# PL_Ethernet.net
KiCad netlist of a schematic drawn in Altium Designer
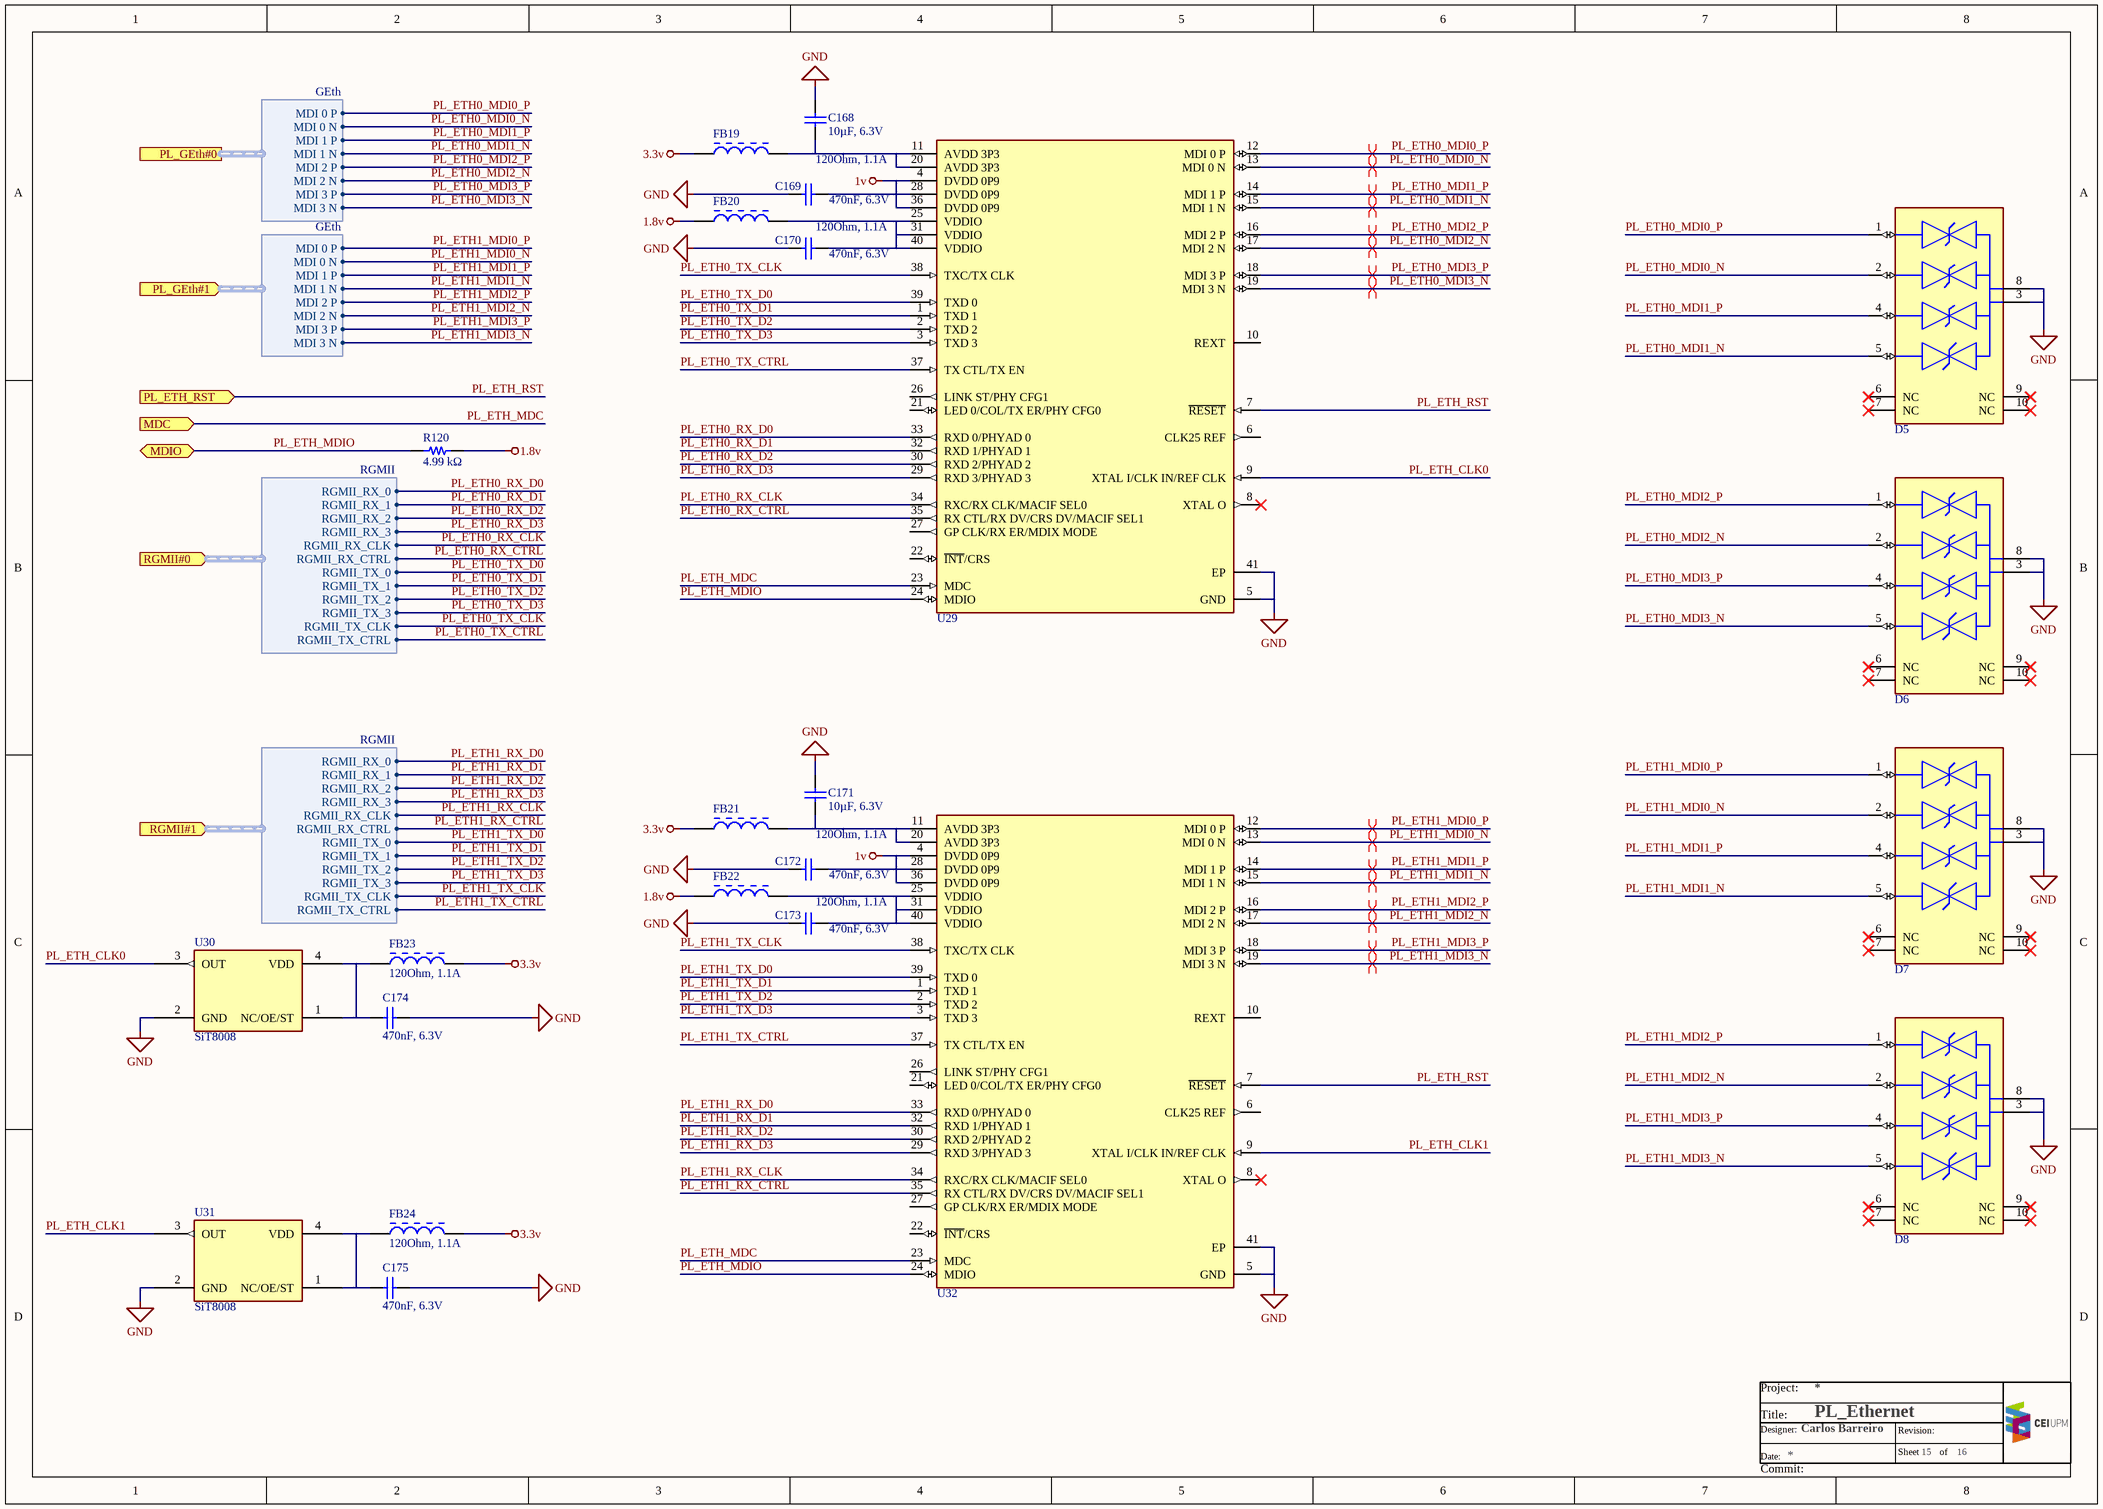
[diagram p0: PL_Ethernet.SchDoc]

(export (version "E")
  (design (tool "Eeschema 10.0.6"))
  (components
    (comp (ref "C168")
      (value "10µF, 6.3V")
      (footprint "WURTH_WCAP-CSGP_0402")
      (description "WCAP-CSGP Multilayer Ceramic Chip Capacitor, General Purpose, size 0402, X5R, 10uF, 6.3V")
      (fields
        (field (name "MANUFACTURER PART NUMBER") "885012105020")
        (field (name "MANUFACTURER") "Wurth Elektronik")
      )
      (libsource (lib "SpaceVNXBaseBoard") (part "885012105020"))
    )
    (comp (ref "C169")
      (value "470nF, 6.3V")
      (footprint "WURTH_WCAP-CSGP_0402")
      (description "WCAP-CSGP Multilayer Ceramic Chip Capacitor, General Purpose, size 0402, X5R, 470nF, 6.3V")
      (fields
        (field (name "MANUFACTURER PART NUMBER") "885012105004")
        (field (name "MANUFACTURER") "Wurth Elektronik")
      )
      (libsource (lib "SpaceVNXBaseBoard") (part "885012105004"))
    )
    (comp (ref "C170")
      (value "470nF, 6.3V")
      (footprint "WURTH_WCAP-CSGP_0402")
      (description "WCAP-CSGP Multilayer Ceramic Chip Capacitor, General Purpose, size 0402, X5R, 470nF, 6.3V")
      (fields
        (field (name "MANUFACTURER PART NUMBER") "885012105004")
        (field (name "MANUFACTURER") "Wurth Elektronik")
      )
      (libsource (lib "SpaceVNXBaseBoard") (part "885012105004"))
    )
    (comp (ref "C171")
      (value "10µF, 6.3V")
      (footprint "WURTH_WCAP-CSGP_0402")
      (description "WCAP-CSGP Multilayer Ceramic Chip Capacitor, General Purpose, size 0402, X5R, 10uF, 6.3V")
      (fields
        (field (name "MANUFACTURER PART NUMBER") "885012105020")
        (field (name "MANUFACTURER") "Wurth Elektronik")
      )
      (libsource (lib "SpaceVNXBaseBoard") (part "885012105020"))
    )
    (comp (ref "C172")
      (value "470nF, 6.3V")
      (footprint "WURTH_WCAP-CSGP_0402")
      (description "WCAP-CSGP Multilayer Ceramic Chip Capacitor, General Purpose, size 0402, X5R, 470nF, 6.3V")
      (fields
        (field (name "MANUFACTURER PART NUMBER") "885012105004")
        (field (name "MANUFACTURER") "Wurth Elektronik")
      )
      (libsource (lib "SpaceVNXBaseBoard") (part "885012105004"))
    )
    (comp (ref "C173")
      (value "470nF, 6.3V")
      (footprint "WURTH_WCAP-CSGP_0402")
      (description "WCAP-CSGP Multilayer Ceramic Chip Capacitor, General Purpose, size 0402, X5R, 470nF, 6.3V")
      (fields
        (field (name "MANUFACTURER PART NUMBER") "885012105004")
        (field (name "MANUFACTURER") "Wurth Elektronik")
      )
      (libsource (lib "SpaceVNXBaseBoard") (part "885012105004"))
    )
    (comp (ref "C174")
      (value "470nF, 6.3V")
      (footprint "WURTH_WCAP-CSGP_0402")
      (description "WCAP-CSGP Multilayer Ceramic Chip Capacitor, General Purpose, size 0402, X5R, 470nF, 6.3V")
      (fields
        (field (name "MANUFACTURER PART NUMBER") "885012105004")
        (field (name "MANUFACTURER") "Wurth Elektronik")
      )
      (libsource (lib "SpaceVNXBaseBoard") (part "885012105004"))
    )
    (comp (ref "C175")
      (value "470nF, 6.3V")
      (footprint "WURTH_WCAP-CSGP_0402")
      (description "WCAP-CSGP Multilayer Ceramic Chip Capacitor, General Purpose, size 0402, X5R, 470nF, 6.3V")
      (fields
        (field (name "MANUFACTURER PART NUMBER") "885012105004")
        (field (name "MANUFACTURER") "Wurth Elektronik")
      )
      (libsource (lib "SpaceVNXBaseBoard") (part "885012105004"))
    )
    (comp (ref "D5")
      (value "ESD204DQAR")
      (footprint "TEXAS_USON10")
      (description "ESD204 4-Channel Low-Capacitance Surge and ESD Protection Diode")
      (libsource (lib "SpaceVNXBaseBoard") (part "ESD204DQAR"))
    )
    (comp (ref "D6")
      (value "ESD204DQAR")
      (footprint "TEXAS_USON10")
      (description "ESD204 4-Channel Low-Capacitance Surge and ESD Protection Diode")
      (libsource (lib "SpaceVNXBaseBoard") (part "ESD204DQAR"))
    )
    (comp (ref "D7")
      (value "ESD204DQAR")
      (footprint "TEXAS_USON10")
      (description "ESD204 4-Channel Low-Capacitance Surge and ESD Protection Diode")
      (libsource (lib "SpaceVNXBaseBoard") (part "ESD204DQAR"))
    )
    (comp (ref "D8")
      (value "ESD204DQAR")
      (footprint "TEXAS_USON10")
      (description "ESD204 4-Channel Low-Capacitance Surge and ESD Protection Diode")
      (libsource (lib "SpaceVNXBaseBoard") (part "ESD204DQAR"))
    )
    (comp (ref "FB19")
      (value "120Ohm, 1.1A")
      (footprint "WURTH-CBF_0402")
      (description "WE-CBF SMT EMI Suppression Ferrite Bead, size 0402, 120Ohm, 1.1A")
      (fields
        (field (name "MANUFACTURER PART NUMBER") "74279271")
        (field (name "MANUFACTURER") "Wurth Elektronik")
      )
      (libsource (lib "SpaceVNXBaseBoard") (part "74279271"))
    )
    (comp (ref "FB20")
      (value "120Ohm, 1.1A")
      (footprint "WURTH-CBF_0402")
      (description "WE-CBF SMT EMI Suppression Ferrite Bead, size 0402, 120Ohm, 1.1A")
      (fields
        (field (name "MANUFACTURER PART NUMBER") "74279271")
        (field (name "MANUFACTURER") "Wurth Elektronik")
      )
      (libsource (lib "SpaceVNXBaseBoard") (part "74279271"))
    )
    (comp (ref "FB21")
      (value "120Ohm, 1.1A")
      (footprint "WURTH-CBF_0402")
      (description "WE-CBF SMT EMI Suppression Ferrite Bead, size 0402, 120Ohm, 1.1A")
      (fields
        (field (name "MANUFACTURER PART NUMBER") "74279271")
        (field (name "MANUFACTURER") "Wurth Elektronik")
      )
      (libsource (lib "SpaceVNXBaseBoard") (part "74279271"))
    )
    (comp (ref "FB22")
      (value "120Ohm, 1.1A")
      (footprint "WURTH-CBF_0402")
      (description "WE-CBF SMT EMI Suppression Ferrite Bead, size 0402, 120Ohm, 1.1A")
      (fields
        (field (name "MANUFACTURER PART NUMBER") "74279271")
        (field (name "MANUFACTURER") "Wurth Elektronik")
      )
      (libsource (lib "SpaceVNXBaseBoard") (part "74279271"))
    )
    (comp (ref "FB23")
      (value "120Ohm, 1.1A")
      (footprint "WURTH-CBF_0402")
      (description "WE-CBF SMT EMI Suppression Ferrite Bead, size 0402, 120Ohm, 1.1A")
      (fields
        (field (name "MANUFACTURER PART NUMBER") "74279271")
        (field (name "MANUFACTURER") "Wurth Elektronik")
      )
      (libsource (lib "SpaceVNXBaseBoard") (part "74279271"))
    )
    (comp (ref "FB24")
      (value "120Ohm, 1.1A")
      (footprint "WURTH-CBF_0402")
      (description "WE-CBF SMT EMI Suppression Ferrite Bead, size 0402, 120Ohm, 1.1A")
      (fields
        (field (name "MANUFACTURER PART NUMBER") "74279271")
        (field (name "MANUFACTURER") "Wurth Elektronik")
      )
      (libsource (lib "SpaceVNXBaseBoard") (part "74279271"))
    )
    (comp (ref "R120")
      (value "4.99 kΩ")
      (footprint "PANASONIC_ERJ2G_0402")
      (description "General Purpose Thick Film Chip Resistors")
      (fields (field (name "MANUFACTURER") "Panasonic"))
      (libsource (lib "SpaceVNXBaseBoard") (part "ERJ2RKF4991X"))
    )
    (comp (ref "U29")
      (value "ADIN1300CCPZ")
      (footprint "ADI_LFCSP40")
      (description "Robust, Industrial, Low Latency and Low Power 10 Mbps, 100 Mbps, and 1 Gbps Ethernet PHY")
      (libsource (lib "SpaceVNXBaseBoard") (part "ADIN1300CCPZ"))
    )
    (comp (ref "U30")
      (value "SiT8008")
      (footprint "SiTime_5032_4")
      (libsource (lib "SpaceVNXBaseBoard") (part "SiT8008"))
    )
    (comp (ref "U31")
      (value "SiT8008")
      (footprint "SiTime_5032_4")
      (libsource (lib "SpaceVNXBaseBoard") (part "SiT8008"))
    )
    (comp (ref "U32")
      (value "ADIN1300CCPZ")
      (footprint "ADI_LFCSP40")
      (description "Robust, Industrial, Low Latency and Low Power 10 Mbps, 100 Mbps, and 1 Gbps Ethernet PHY")
      (libsource (lib "SpaceVNXBaseBoard") (part "ADIN1300CCPZ"))
    )
  )
  (nets
    (net (code "3") (name "/PL_ETH0_MDI0_N") (class "Default")
      (node (ref "D5") (pin "2") (pinfunction "IO2_2") (pintype "bidirectional"))
      (node (ref "U29") (pin "13") (pinfunction "MDI_0_N_13") (pintype "bidirectional"))
    )
    (net (code "4") (name "/PL_ETH0_MDI0_P") (class "Default")
      (node (ref "D5") (pin "1") (pinfunction "IO1_1") (pintype "bidirectional"))
      (node (ref "U29") (pin "12") (pinfunction "MDI_0_P_12") (pintype "bidirectional"))
    )
    (net (code "5") (name "/PL_ETH0_MDI1_N") (class "Default")
      (node (ref "D5") (pin "5") (pinfunction "IO4_5") (pintype "bidirectional"))
      (node (ref "U29") (pin "15") (pinfunction "MDI_1_N_15") (pintype "bidirectional"))
    )
    (net (code "6") (name "/PL_ETH0_MDI1_P") (class "Default")
      (node (ref "D5") (pin "4") (pinfunction "IO3_4") (pintype "bidirectional"))
      (node (ref "U29") (pin "14") (pinfunction "MDI_1_P_14") (pintype "bidirectional"))
    )
    (net (code "7") (name "/PL_ETH0_MDI2_N") (class "Default")
      (node (ref "D6") (pin "2") (pinfunction "IO2_2") (pintype "bidirectional"))
      (node (ref "U29") (pin "17") (pinfunction "MDI_2_N_17") (pintype "bidirectional"))
    )
    (net (code "8") (name "/PL_ETH0_MDI2_P") (class "Default")
      (node (ref "D6") (pin "1") (pinfunction "IO1_1") (pintype "bidirectional"))
      (node (ref "U29") (pin "16") (pinfunction "MDI_2_P_16") (pintype "bidirectional"))
    )
    (net (code "9") (name "/PL_ETH0_MDI3_N") (class "Default")
      (node (ref "D6") (pin "5") (pinfunction "IO4_5") (pintype "bidirectional"))
      (node (ref "U29") (pin "19") (pinfunction "MDI_3_N_19") (pintype "bidirectional"))
    )
    (net (code "10") (name "/PL_ETH0_MDI3_P") (class "Default")
      (node (ref "D6") (pin "4") (pinfunction "IO3_4") (pintype "bidirectional"))
      (node (ref "U29") (pin "18") (pinfunction "MDI_3_P_18") (pintype "bidirectional"))
    )
    (net (code "11") (name "/PL_ETH0_RX_CLK") (class "Default")
      (node (ref "U29") (pin "34") (pinfunction "RXC/RX_CLK/MACIF_SEL0_34") (pintype "output"))
    )
    (net (code "12") (name "/PL_ETH0_RX_CTRL") (class "Default")
      (node (ref "U29") (pin "35") (pinfunction "RX_CTL/RX_DV/CRS_DV/MACIF_SEL1_35") (pintype "output"))
    )
    (net (code "13") (name "/PL_ETH0_RX_D0") (class "Default")
      (node (ref "U29") (pin "33") (pinfunction "RXD_0/PHYAD_0_33") (pintype "output"))
    )
    (net (code "14") (name "/PL_ETH0_RX_D1") (class "Default")
      (node (ref "U29") (pin "32") (pinfunction "RXD_1/PHYAD_1_32") (pintype "output"))
    )
    (net (code "15") (name "/PL_ETH0_RX_D2") (class "Default")
      (node (ref "U29") (pin "30") (pinfunction "RXD_2/PHYAD_2_30") (pintype "output"))
    )
    (net (code "16") (name "/PL_ETH0_RX_D3") (class "Default")
      (node (ref "U29") (pin "29") (pinfunction "RXD_3/PHYAD_3_29") (pintype "output"))
    )
    (net (code "17") (name "/PL_ETH0_TX_CLK") (class "Default")
      (node (ref "U29") (pin "38") (pinfunction "TXC/TX_CLK_38") (pintype "input"))
    )
    (net (code "18") (name "/PL_ETH0_TX_CTRL") (class "Default")
      (node (ref "U29") (pin "37") (pinfunction "TX_CTL/TX_EN_37") (pintype "input"))
    )
    (net (code "19") (name "/PL_ETH0_TX_D0") (class "Default")
      (node (ref "U29") (pin "39") (pinfunction "TXD_0_39") (pintype "input"))
    )
    (net (code "20") (name "/PL_ETH0_TX_D1") (class "Default")
      (node (ref "U29") (pin "1") (pinfunction "TXD_1_1") (pintype "input"))
    )
    (net (code "21") (name "/PL_ETH0_TX_D2") (class "Default")
      (node (ref "U29") (pin "2") (pinfunction "TXD_2_2") (pintype "input"))
    )
    (net (code "22") (name "/PL_ETH0_TX_D3") (class "Default")
      (node (ref "U29") (pin "3") (pinfunction "TXD_3_3") (pintype "input"))
    )
    (net (code "23") (name "/PL_ETH1_MDI0_N") (class "Default")
      (node (ref "D7") (pin "2") (pinfunction "IO2_2") (pintype "bidirectional"))
      (node (ref "U32") (pin "13") (pinfunction "MDI_0_N_13") (pintype "bidirectional"))
    )
    (net (code "24") (name "/PL_ETH1_MDI0_P") (class "Default")
      (node (ref "D7") (pin "1") (pinfunction "IO1_1") (pintype "bidirectional"))
      (node (ref "U32") (pin "12") (pinfunction "MDI_0_P_12") (pintype "bidirectional"))
    )
    (net (code "25") (name "/PL_ETH1_MDI1_N") (class "Default")
      (node (ref "D7") (pin "5") (pinfunction "IO4_5") (pintype "bidirectional"))
      (node (ref "U32") (pin "15") (pinfunction "MDI_1_N_15") (pintype "bidirectional"))
    )
    (net (code "26") (name "/PL_ETH1_MDI1_P") (class "Default")
      (node (ref "D7") (pin "4") (pinfunction "IO3_4") (pintype "bidirectional"))
      (node (ref "U32") (pin "14") (pinfunction "MDI_1_P_14") (pintype "bidirectional"))
    )
    (net (code "27") (name "/PL_ETH1_MDI2_N") (class "Default")
      (node (ref "D8") (pin "2") (pinfunction "IO2_2") (pintype "bidirectional"))
      (node (ref "U32") (pin "17") (pinfunction "MDI_2_N_17") (pintype "bidirectional"))
    )
    (net (code "28") (name "/PL_ETH1_MDI2_P") (class "Default")
      (node (ref "D8") (pin "1") (pinfunction "IO1_1") (pintype "bidirectional"))
      (node (ref "U32") (pin "16") (pinfunction "MDI_2_P_16") (pintype "bidirectional"))
    )
    (net (code "29") (name "/PL_ETH1_MDI3_N") (class "Default")
      (node (ref "D8") (pin "5") (pinfunction "IO4_5") (pintype "bidirectional"))
      (node (ref "U32") (pin "19") (pinfunction "MDI_3_N_19") (pintype "bidirectional"))
    )
    (net (code "30") (name "/PL_ETH1_MDI3_P") (class "Default")
      (node (ref "D8") (pin "4") (pinfunction "IO3_4") (pintype "bidirectional"))
      (node (ref "U32") (pin "18") (pinfunction "MDI_3_P_18") (pintype "bidirectional"))
    )
    (net (code "31") (name "/PL_ETH1_RX_CLK") (class "Default")
      (node (ref "U32") (pin "34") (pinfunction "RXC/RX_CLK/MACIF_SEL0_34") (pintype "output"))
    )
    (net (code "32") (name "/PL_ETH1_RX_CTRL") (class "Default")
      (node (ref "U32") (pin "35") (pinfunction "RX_CTL/RX_DV/CRS_DV/MACIF_SEL1_35") (pintype "output"))
    )
    (net (code "33") (name "/PL_ETH1_RX_D0") (class "Default")
      (node (ref "U32") (pin "33") (pinfunction "RXD_0/PHYAD_0_33") (pintype "output"))
    )
    (net (code "34") (name "/PL_ETH1_RX_D1") (class "Default")
      (node (ref "U32") (pin "32") (pinfunction "RXD_1/PHYAD_1_32") (pintype "output"))
    )
    (net (code "35") (name "/PL_ETH1_RX_D2") (class "Default")
      (node (ref "U32") (pin "30") (pinfunction "RXD_2/PHYAD_2_30") (pintype "output"))
    )
    (net (code "36") (name "/PL_ETH1_RX_D3") (class "Default")
      (node (ref "U32") (pin "29") (pinfunction "RXD_3/PHYAD_3_29") (pintype "output"))
    )
    (net (code "37") (name "/PL_ETH1_TX_CLK") (class "Default")
      (node (ref "U32") (pin "38") (pinfunction "TXC/TX_CLK_38") (pintype "input"))
    )
    (net (code "38") (name "/PL_ETH1_TX_CTRL") (class "Default")
      (node (ref "U32") (pin "37") (pinfunction "TX_CTL/TX_EN_37") (pintype "input"))
    )
    (net (code "39") (name "/PL_ETH1_TX_D0") (class "Default")
      (node (ref "U32") (pin "39") (pinfunction "TXD_0_39") (pintype "input"))
    )
    (net (code "40") (name "/PL_ETH1_TX_D1") (class "Default")
      (node (ref "U32") (pin "1") (pinfunction "TXD_1_1") (pintype "input"))
    )
    (net (code "41") (name "/PL_ETH1_TX_D2") (class "Default")
      (node (ref "U32") (pin "2") (pinfunction "TXD_2_2") (pintype "input"))
    )
    (net (code "42") (name "/PL_ETH1_TX_D3") (class "Default")
      (node (ref "U32") (pin "3") (pinfunction "TXD_3_3") (pintype "input"))
    )
    (net (code "43") (name "/PL_ETH_CLK0") (class "Default")
      (node (ref "U29") (pin "9") (pinfunction "XTAL_I/CLK_IN/REF_CLK_9") (pintype "input"))
      (node (ref "U30") (pin "3") (pinfunction "OUT_3") (pintype "output"))
    )
    (net (code "44") (name "/PL_ETH_CLK1") (class "Default")
      (node (ref "U31") (pin "3") (pinfunction "OUT_3") (pintype "output"))
      (node (ref "U32") (pin "9") (pinfunction "XTAL_I/CLK_IN/REF_CLK_9") (pintype "input"))
    )
    (net (code "45") (name "/PL_ETH_MDC") (class "Default")
      (node (ref "U29") (pin "23") (pinfunction "MDC_23") (pintype "input"))
      (node (ref "U32") (pin "23") (pinfunction "MDC_23") (pintype "input"))
    )
    (net (code "46") (name "/PL_ETH_MDIO") (class "Default")
      (node (ref "R120") (pin "1") (pinfunction "1_1") (pintype "passive"))
      (node (ref "U29") (pin "24") (pinfunction "MDIO_24") (pintype "bidirectional"))
      (node (ref "U32") (pin "24") (pinfunction "MDIO_24") (pintype "bidirectional"))
    )
    (net (code "47") (name "/PL_ETH_RST") (class "Default")
      (node (ref "U29") (pin "7") (pinfunction "~{RESET}_7") (pintype "input"))
      (node (ref "U32") (pin "7") (pinfunction "~{RESET}_7") (pintype "input"))
    )
    (net (code "50") (name "1.8v") (class "Default")
      (node (ref "FB20") (pin "1") (pinfunction "1_1") (pintype "passive"))
      (node (ref "FB22") (pin "1") (pinfunction "1_1") (pintype "passive"))
      (node (ref "R120") (pin "2") (pinfunction "2_2") (pintype "passive"))
    )
    (net (code "51") (name "1v") (class "Default")
      (node (ref "C169") (pin "2") (pinfunction "2_2") (pintype "passive"))
      (node (ref "C172") (pin "2") (pinfunction "2_2") (pintype "passive"))
      (node (ref "U29") (pin "28") (pinfunction "DVDD_0P9_28") (pintype "power_in"))
      (node (ref "U29") (pin "36") (pinfunction "DVDD_0P9_36") (pintype "power_in"))
      (node (ref "U29") (pin "4") (pinfunction "DVDD_0P9_4") (pintype "power_in"))
      (node (ref "U32") (pin "28") (pinfunction "DVDD_0P9_28") (pintype "power_in"))
      (node (ref "U32") (pin "36") (pinfunction "DVDD_0P9_36") (pintype "power_in"))
      (node (ref "U32") (pin "4") (pinfunction "DVDD_0P9_4") (pintype "power_in"))
    )
    (net (code "52") (name "3.3v") (class "Default")
      (node (ref "FB19") (pin "1") (pinfunction "1_1") (pintype "passive"))
      (node (ref "FB21") (pin "1") (pinfunction "1_1") (pintype "passive"))
      (node (ref "FB23") (pin "2") (pinfunction "2_2") (pintype "passive"))
      (node (ref "FB24") (pin "2") (pinfunction "2_2") (pintype "passive"))
    )
    (net (code "53") (name "GND") (class "Default")
      (node (ref "C168") (pin "2") (pinfunction "2_2") (pintype "passive"))
      (node (ref "C169") (pin "1") (pinfunction "1_1") (pintype "passive"))
      (node (ref "C170") (pin "1") (pinfunction "1_1") (pintype "passive"))
      (node (ref "C171") (pin "2") (pinfunction "2_2") (pintype "passive"))
      (node (ref "C172") (pin "1") (pinfunction "1_1") (pintype "passive"))
      (node (ref "C173") (pin "1") (pinfunction "1_1") (pintype "passive"))
      (node (ref "C174") (pin "1") (pinfunction "1_1") (pintype "passive"))
      (node (ref "C175") (pin "1") (pinfunction "1_1") (pintype "passive"))
      (node (ref "D5") (pin "3") (pinfunction "GND_3") (pintype "power_in"))
      (node (ref "D5") (pin "8") (pinfunction "GND_8") (pintype "power_in"))
      (node (ref "D6") (pin "3") (pinfunction "GND_3") (pintype "power_in"))
      (node (ref "D6") (pin "8") (pinfunction "GND_8") (pintype "power_in"))
      (node (ref "D7") (pin "3") (pinfunction "GND_3") (pintype "power_in"))
      (node (ref "D7") (pin "8") (pinfunction "GND_8") (pintype "power_in"))
      (node (ref "D8") (pin "3") (pinfunction "GND_3") (pintype "power_in"))
      (node (ref "D8") (pin "8") (pinfunction "GND_8") (pintype "power_in"))
      (node (ref "U29") (pin "41") (pinfunction "EP_41") (pintype "power_in"))
      (node (ref "U29") (pin "5") (pinfunction "GND_5") (pintype "power_in"))
      (node (ref "U30") (pin "2") (pinfunction "GND_2") (pintype "passive"))
      (node (ref "U31") (pin "2") (pinfunction "GND_2") (pintype "passive"))
      (node (ref "U32") (pin "41") (pinfunction "EP_41") (pintype "power_in"))
      (node (ref "U32") (pin "5") (pinfunction "GND_5") (pintype "power_in"))
    )
    (net (code "54") (name "Net-(C168-Pad1)") (class "Default")
      (node (ref "C168") (pin "1") (pinfunction "1_1") (pintype "passive"))
      (node (ref "FB19") (pin "2") (pinfunction "2_2") (pintype "passive"))
      (node (ref "U29") (pin "11") (pinfunction "AVDD_3P3_11") (pintype "power_in"))
      (node (ref "U29") (pin "20") (pinfunction "AVDD_3P3_20") (pintype "power_in"))
    )
    (net (code "55") (name "Net-(C170-Pad2)") (class "Default")
      (node (ref "C170") (pin "2") (pinfunction "2_2") (pintype "passive"))
      (node (ref "FB20") (pin "2") (pinfunction "2_2") (pintype "passive"))
      (node (ref "U29") (pin "25") (pinfunction "VDDIO_25") (pintype "power_in"))
      (node (ref "U29") (pin "31") (pinfunction "VDDIO_31") (pintype "power_in"))
      (node (ref "U29") (pin "40") (pinfunction "VDDIO_40") (pintype "power_in"))
    )
    (net (code "56") (name "Net-(C171-Pad1)") (class "Default")
      (node (ref "C171") (pin "1") (pinfunction "1_1") (pintype "passive"))
      (node (ref "FB21") (pin "2") (pinfunction "2_2") (pintype "passive"))
      (node (ref "U32") (pin "11") (pinfunction "AVDD_3P3_11") (pintype "power_in"))
      (node (ref "U32") (pin "20") (pinfunction "AVDD_3P3_20") (pintype "power_in"))
    )
    (net (code "57") (name "Net-(C173-Pad2)") (class "Default")
      (node (ref "C173") (pin "2") (pinfunction "2_2") (pintype "passive"))
      (node (ref "FB22") (pin "2") (pinfunction "2_2") (pintype "passive"))
      (node (ref "U32") (pin "25") (pinfunction "VDDIO_25") (pintype "power_in"))
      (node (ref "U32") (pin "31") (pinfunction "VDDIO_31") (pintype "power_in"))
      (node (ref "U32") (pin "40") (pinfunction "VDDIO_40") (pintype "power_in"))
    )
    (net (code "58") (name "Net-(U30-NC{slash}OE{slash}ST)") (class "Default")
      (node (ref "C174") (pin "2") (pinfunction "2_2") (pintype "passive"))
      (node (ref "FB23") (pin "1") (pinfunction "1_1") (pintype "passive"))
      (node (ref "U30") (pin "1") (pinfunction "NC/OE/ST_1") (pintype "passive"))
      (node (ref "U30") (pin "4") (pinfunction "VDD_4") (pintype "passive"))
    )
    (net (code "59") (name "Net-(U31-NC{slash}OE{slash}ST)") (class "Default")
      (node (ref "C175") (pin "2") (pinfunction "2_2") (pintype "passive"))
      (node (ref "FB24") (pin "1") (pinfunction "1_1") (pintype "passive"))
      (node (ref "U31") (pin "1") (pinfunction "NC/OE/ST_1") (pintype "passive"))
      (node (ref "U31") (pin "4") (pinfunction "VDD_4") (pintype "passive"))
    )
    (net (code "60") (name "unconnected-(D5-NC-Pad6)") (class "Default")
      (node (ref "D5") (pin "6") (pinfunction "NC_6") (pintype "passive+no_connect"))
    )
    (net (code "61") (name "unconnected-(D5-NC-Pad7)") (class "Default")
      (node (ref "D5") (pin "7") (pinfunction "NC_7") (pintype "passive+no_connect"))
    )
    (net (code "62") (name "unconnected-(D5-NC-Pad9)") (class "Default")
      (node (ref "D5") (pin "9") (pinfunction "NC_9") (pintype "passive+no_connect"))
    )
    (net (code "63") (name "unconnected-(D5-NC-Pad10)") (class "Default")
      (node (ref "D5") (pin "10") (pinfunction "NC_10") (pintype "passive+no_connect"))
    )
    (net (code "64") (name "unconnected-(D6-NC-Pad6)") (class "Default")
      (node (ref "D6") (pin "6") (pinfunction "NC_6") (pintype "passive+no_connect"))
    )
    (net (code "65") (name "unconnected-(D6-NC-Pad7)") (class "Default")
      (node (ref "D6") (pin "7") (pinfunction "NC_7") (pintype "passive+no_connect"))
    )
    (net (code "66") (name "unconnected-(D6-NC-Pad9)") (class "Default")
      (node (ref "D6") (pin "9") (pinfunction "NC_9") (pintype "passive+no_connect"))
    )
    (net (code "67") (name "unconnected-(D6-NC-Pad10)") (class "Default")
      (node (ref "D6") (pin "10") (pinfunction "NC_10") (pintype "passive+no_connect"))
    )
    (net (code "68") (name "unconnected-(D7-NC-Pad6)") (class "Default")
      (node (ref "D7") (pin "6") (pinfunction "NC_6") (pintype "passive+no_connect"))
    )
    (net (code "69") (name "unconnected-(D7-NC-Pad7)") (class "Default")
      (node (ref "D7") (pin "7") (pinfunction "NC_7") (pintype "passive+no_connect"))
    )
    (net (code "70") (name "unconnected-(D7-NC-Pad9)") (class "Default")
      (node (ref "D7") (pin "9") (pinfunction "NC_9") (pintype "passive+no_connect"))
    )
    (net (code "71") (name "unconnected-(D7-NC-Pad10)") (class "Default")
      (node (ref "D7") (pin "10") (pinfunction "NC_10") (pintype "passive+no_connect"))
    )
    (net (code "72") (name "unconnected-(D8-NC-Pad6)") (class "Default")
      (node (ref "D8") (pin "6") (pinfunction "NC_6") (pintype "passive+no_connect"))
    )
    (net (code "73") (name "unconnected-(D8-NC-Pad7)") (class "Default")
      (node (ref "D8") (pin "7") (pinfunction "NC_7") (pintype "passive+no_connect"))
    )
    (net (code "74") (name "unconnected-(D8-NC-Pad9)") (class "Default")
      (node (ref "D8") (pin "9") (pinfunction "NC_9") (pintype "passive+no_connect"))
    )
    (net (code "75") (name "unconnected-(D8-NC-Pad10)") (class "Default")
      (node (ref "D8") (pin "10") (pinfunction "NC_10") (pintype "passive+no_connect"))
    )
    (net (code "76") (name "unconnected-(U29-CLK25_REF-Pad6)") (class "Default")
      (node (ref "U29") (pin "6") (pinfunction "CLK25_REF_6") (pintype "output"))
    )
    (net (code "77") (name "unconnected-(U29-GP_CLK{slash}RX_ER{slash}MDIX_MODE-Pad27)") (class "Default")
      (node (ref "U29") (pin "27") (pinfunction "GP_CLK/RX_ER/MDIX_MODE_27") (pintype "output"))
    )
    (net (code "78") (name "unconnected-(U29-LED_0{slash}COL{slash}TX_ER{slash}PHY_CFG0-Pad21)") (class "Default")
      (node (ref "U29") (pin "21") (pinfunction "LED_0/COL/TX_ER/PHY_CFG0_21") (pintype "bidirectional"))
    )
    (net (code "79") (name "unconnected-(U29-LINK_ST{slash}PHY_CFG1-Pad26)") (class "Default")
      (node (ref "U29") (pin "26") (pinfunction "LINK_ST/PHY_CFG1_26") (pintype "output"))
    )
    (net (code "80") (name "unconnected-(U29-REXT-Pad10)") (class "Default")
      (node (ref "U29") (pin "10") (pinfunction "REXT_10") (pintype "passive"))
    )
    (net (code "81") (name "unconnected-(U29-XTAL_O-Pad8)") (class "Default")
      (node (ref "U29") (pin "8") (pinfunction "XTAL_O_8") (pintype "output+no_connect"))
    )
    (net (code "82") (name "unconnected-(U29-~{INT}{slash}CRS-Pad22)") (class "Default")
      (node (ref "U29") (pin "22") (pinfunction "~{INT}/CRS_22") (pintype "bidirectional"))
    )
    (net (code "83") (name "unconnected-(U32-CLK25_REF-Pad6)") (class "Default")
      (node (ref "U32") (pin "6") (pinfunction "CLK25_REF_6") (pintype "output"))
    )
    (net (code "84") (name "unconnected-(U32-GP_CLK{slash}RX_ER{slash}MDIX_MODE-Pad27)") (class "Default")
      (node (ref "U32") (pin "27") (pinfunction "GP_CLK/RX_ER/MDIX_MODE_27") (pintype "output"))
    )
    (net (code "85") (name "unconnected-(U32-LED_0{slash}COL{slash}TX_ER{slash}PHY_CFG0-Pad21)") (class "Default")
      (node (ref "U32") (pin "21") (pinfunction "LED_0/COL/TX_ER/PHY_CFG0_21") (pintype "bidirectional"))
    )
    (net (code "86") (name "unconnected-(U32-LINK_ST{slash}PHY_CFG1-Pad26)") (class "Default")
      (node (ref "U32") (pin "26") (pinfunction "LINK_ST/PHY_CFG1_26") (pintype "output"))
    )
    (net (code "87") (name "unconnected-(U32-REXT-Pad10)") (class "Default")
      (node (ref "U32") (pin "10") (pinfunction "REXT_10") (pintype "passive"))
    )
    (net (code "88") (name "unconnected-(U32-XTAL_O-Pad8)") (class "Default")
      (node (ref "U32") (pin "8") (pinfunction "XTAL_O_8") (pintype "output+no_connect"))
    )
    (net (code "89") (name "unconnected-(U32-~{INT}{slash}CRS-Pad22)") (class "Default")
      (node (ref "U32") (pin "22") (pinfunction "~{INT}/CRS_22") (pintype "bidirectional"))
    )
  )
)
